# M310A.net
KiCad netlist of a schematic drawn in EAGLE
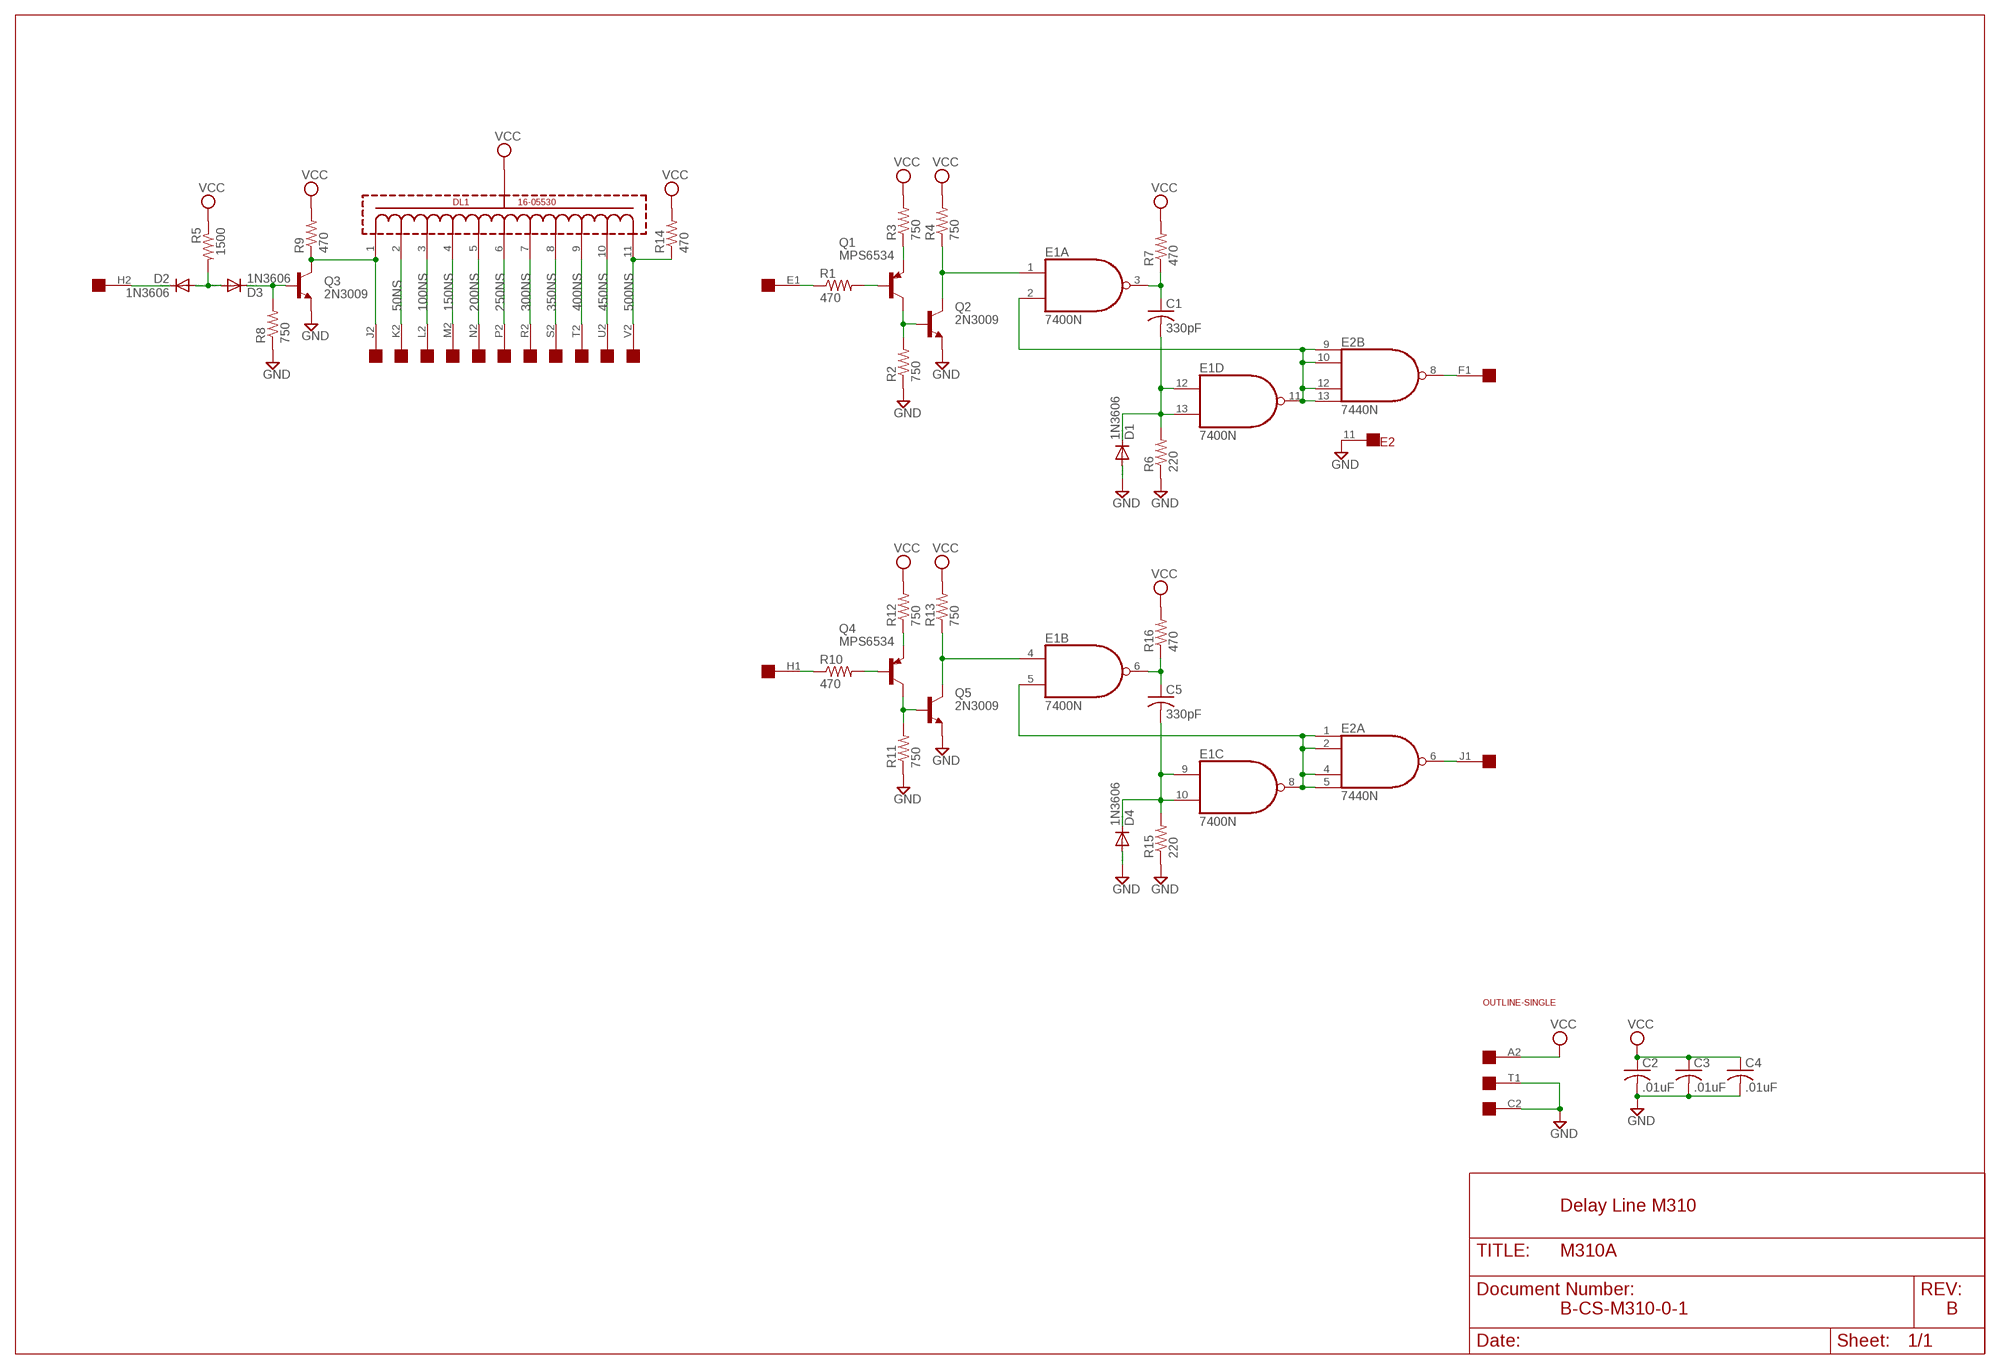
[diagram p0: schematic, sheet 1]

(export (version "E")
  (design (tool "Eeschema 10.0.6"))
  (components
    (comp (ref "C1")
      (value "330pF")
      (footprint "eagle-import:C050-025X075")
      (libsource (lib "eagle-import") (part "C-US050-025X075"))
    )
    (comp (ref "C2")
      (value ".01uF")
      (footprint "eagle-import:C050-025X075")
      (libsource (lib "eagle-import") (part "C-US050-025X075"))
    )
    (comp (ref "C3")
      (value ".01uF")
      (footprint "eagle-import:C050-025X075")
      (libsource (lib "eagle-import") (part "C-US050-025X075"))
    )
    (comp (ref "C4")
      (value ".01uF")
      (footprint "eagle-import:C050-025X075")
      (libsource (lib "eagle-import") (part "C-US050-025X075"))
    )
    (comp (ref "C5")
      (value "330pF")
      (footprint "eagle-import:C050-025X075")
      (libsource (lib "eagle-import") (part "C-US050-025X075"))
    )
    (comp (ref "D1")
      (value "1N3606")
      (footprint "eagle-import:DO35-10")
      (libsource (lib "eagle-import") (part "1N4148DO35-10"))
    )
    (comp (ref "D2")
      (value "1N3606")
      (footprint "eagle-import:DO35-10")
      (libsource (lib "eagle-import") (part "1N4148DO35-10"))
    )
    (comp (ref "D3")
      (value "1N3606")
      (footprint "eagle-import:DO35-10")
      (libsource (lib "eagle-import") (part "1N4148DO35-10"))
    )
    (comp (ref "D4")
      (value "1N3606")
      (footprint "eagle-import:DO35-10")
      (libsource (lib "eagle-import") (part "1N4148DO35-10"))
    )
    (comp (ref "DL1")
      (value "16-05530")
      (footprint "eagle-import:16-05530")
      (libsource (lib "eagle-import") (part "16-05530"))
    )
    (comp (ref "E1")
      (value "7400N")
      (footprint "eagle-import:DIL14")
      (libsource (lib "eagle-import") (part "7400N"))
    )
    (comp (ref "E2")
      (value "7440N")
      (footprint "eagle-import:DIL14")
      (libsource (lib "eagle-import") (part "7420NS"))
    )
    (comp (ref "Q1")
      (value "MPS6534")
      (footprint "eagle-import:TO39")
      (libsource (lib "eagle-import") (part "2N3637"))
    )
    (comp (ref "Q2")
      (value "2N3009")
      (footprint "eagle-import:TO39")
      (libsource (lib "eagle-import") (part "-NPN-TO39-EBC2N3019"))
    )
    (comp (ref "Q3")
      (value "2N3009")
      (footprint "eagle-import:TO39")
      (libsource (lib "eagle-import") (part "-NPN-TO39-EBC2N3019"))
    )
    (comp (ref "Q4")
      (value "MPS6534")
      (footprint "eagle-import:TO39")
      (libsource (lib "eagle-import") (part "2N3637"))
    )
    (comp (ref "Q5")
      (value "2N3009")
      (footprint "eagle-import:TO39")
      (libsource (lib "eagle-import") (part "-NPN-TO39-EBC2N3019"))
    )
    (comp (ref "R1")
      (value "470")
      (footprint "eagle-import:0207_10")
      (libsource (lib "eagle-import") (part "R-US_0207/10"))
    )
    (comp (ref "R2")
      (value "750")
      (footprint "eagle-import:0207_10")
      (libsource (lib "eagle-import") (part "R-US_0207/10"))
    )
    (comp (ref "R3")
      (value "750")
      (footprint "eagle-import:0207_10")
      (libsource (lib "eagle-import") (part "R-US_0207/10"))
    )
    (comp (ref "R4")
      (value "750")
      (footprint "eagle-import:0207_10")
      (libsource (lib "eagle-import") (part "R-US_0207/10"))
    )
    (comp (ref "R5")
      (value "1500")
      (footprint "eagle-import:0207_10")
      (libsource (lib "eagle-import") (part "R-US_0207/10"))
    )
    (comp (ref "R6")
      (value "220")
      (footprint "eagle-import:0207_10")
      (libsource (lib "eagle-import") (part "R-US_0207/10"))
    )
    (comp (ref "R7")
      (value "470")
      (footprint "eagle-import:0207_10")
      (libsource (lib "eagle-import") (part "R-US_0207/10"))
    )
    (comp (ref "R8")
      (value "750")
      (footprint "eagle-import:0207_10")
      (libsource (lib "eagle-import") (part "R-US_0207/10"))
    )
    (comp (ref "R9")
      (value "470")
      (footprint "eagle-import:0207_10")
      (libsource (lib "eagle-import") (part "R-US_0207/10"))
    )
    (comp (ref "R10")
      (value "470")
      (footprint "eagle-import:0207_10")
      (libsource (lib "eagle-import") (part "R-US_0207/10"))
    )
    (comp (ref "R11")
      (value "750")
      (footprint "eagle-import:0207_10")
      (libsource (lib "eagle-import") (part "R-US_0207/10"))
    )
    (comp (ref "R12")
      (value "750")
      (footprint "eagle-import:0207_10")
      (libsource (lib "eagle-import") (part "R-US_0207/10"))
    )
    (comp (ref "R13")
      (value "750")
      (footprint "eagle-import:0207_10")
      (libsource (lib "eagle-import") (part "R-US_0207/10"))
    )
    (comp (ref "R14")
      (value "470")
      (footprint "eagle-import:0207_10")
      (libsource (lib "eagle-import") (part "R-US_0207/10"))
    )
    (comp (ref "R15")
      (value "220")
      (footprint "eagle-import:0207_10")
      (libsource (lib "eagle-import") (part "R-US_0207/10"))
    )
    (comp (ref "R16")
      (value "470")
      (footprint "eagle-import:0207_10")
      (libsource (lib "eagle-import") (part "R-US_0207/10"))
    )
    (comp (ref "U$1")
      (value "OUTLINE-SINGLE")
      (footprint "eagle-import:SINGLE")
      (libsource (lib "eagle-import") (part "OUTLINE-SINGLE"))
    )
    (comp (ref "U$4")
      (value "SINGLE")
      (footprint "eagle-import:EDGE-CON2")
      (libsource (lib "eagle-import") (part "SINGLE"))
    )
  )
  (nets
    (net (code "1") (name "/50NS") (class "Default")
      (node (ref "DL1") (pin "2") (pinfunction "5_2") (pintype "passive"))
      (node (ref "U$4") (pin "K2") (pinfunction "1_K2") (pintype "bidirectional"))
    )
    (net (code "2") (name "/100NS") (class "Default")
      (node (ref "DL1") (pin "3") (pinfunction "10_3") (pintype "passive"))
      (node (ref "U$4") (pin "L2") (pinfunction "1_L2") (pintype "bidirectional"))
    )
    (net (code "3") (name "/150NS") (class "Default")
      (node (ref "DL1") (pin "4") (pinfunction "15_4") (pintype "passive"))
      (node (ref "U$4") (pin "M2") (pinfunction "1_M2") (pintype "bidirectional"))
    )
    (net (code "4") (name "/200NS") (class "Default")
      (node (ref "DL1") (pin "5") (pinfunction "20_5") (pintype "passive"))
      (node (ref "U$4") (pin "N2") (pinfunction "1_N2") (pintype "bidirectional"))
    )
    (net (code "5") (name "/250NS") (class "Default")
      (node (ref "DL1") (pin "6") (pinfunction "25_6") (pintype "passive"))
      (node (ref "U$4") (pin "P2") (pinfunction "1_P2") (pintype "bidirectional"))
    )
    (net (code "6") (name "/300NS") (class "Default")
      (node (ref "DL1") (pin "7") (pinfunction "30_7") (pintype "passive"))
      (node (ref "U$4") (pin "R2") (pinfunction "1_R2") (pintype "bidirectional"))
    )
    (net (code "7") (name "/350NS") (class "Default")
      (node (ref "DL1") (pin "8") (pinfunction "35_8") (pintype "passive"))
      (node (ref "U$4") (pin "S2") (pinfunction "1_S2") (pintype "bidirectional"))
    )
    (net (code "8") (name "/400NS") (class "Default")
      (node (ref "DL1") (pin "9") (pinfunction "40_9") (pintype "passive"))
      (node (ref "U$4") (pin "T2") (pinfunction "1_T2") (pintype "bidirectional"))
    )
    (net (code "9") (name "/450NS") (class "Default")
      (node (ref "DL1") (pin "10") (pinfunction "45_10") (pintype "passive"))
      (node (ref "U$4") (pin "U2") (pinfunction "1_U2") (pintype "bidirectional"))
    )
    (net (code "10") (name "/500NS") (class "Default")
      (node (ref "DL1") (pin "11") (pinfunction "50_11") (pintype "passive"))
      (node (ref "R14") (pin "1") (pinfunction "1_1") (pintype "passive"))
      (node (ref "U$4") (pin "V2") (pinfunction "1_V2") (pintype "bidirectional"))
    )
    (net (code "11") (name "GND") (class "Default")
      (node (ref "C2") (pin "2") (pinfunction "2_2") (pintype "passive"))
      (node (ref "C3") (pin "2") (pinfunction "2_2") (pintype "passive"))
      (node (ref "C4") (pin "2") (pinfunction "2_2") (pintype "passive"))
      (node (ref "D1") (pin "A") (pinfunction "A_A") (pintype "passive"))
      (node (ref "D4") (pin "A") (pinfunction "A_A") (pintype "passive"))
      (node (ref "E2") (pin "11") (pinfunction "NC_11") (pintype "passive"))
      (node (ref "Q2") (pin "1") (pinfunction "E_1") (pintype "passive"))
      (node (ref "Q3") (pin "1") (pinfunction "E_1") (pintype "passive"))
      (node (ref "Q5") (pin "1") (pinfunction "E_1") (pintype "passive"))
      (node (ref "R11") (pin "1") (pinfunction "1_1") (pintype "passive"))
      (node (ref "R15") (pin "1") (pinfunction "1_1") (pintype "passive"))
      (node (ref "R2") (pin "1") (pinfunction "1_1") (pintype "passive"))
      (node (ref "R6") (pin "1") (pinfunction "1_1") (pintype "passive"))
      (node (ref "R8") (pin "1") (pinfunction "1_1") (pintype "passive"))
      (node (ref "U$4") (pin "C2") (pinfunction "1_C2") (pintype "bidirectional"))
      (node (ref "U$4") (pin "T1") (pinfunction "1_T1") (pintype "bidirectional"))
    )
    (net (code "12") (name "Net-(D2-PadA)") (class "Default")
      (node (ref "D2") (pin "A") (pinfunction "A_A") (pintype "passive"))
      (node (ref "D3") (pin "A") (pinfunction "A_A") (pintype "passive"))
      (node (ref "R5") (pin "2") (pinfunction "2_2") (pintype "passive"))
    )
    (net (code "13") (name "Net-(DL1-0)") (class "Default")
      (node (ref "DL1") (pin "1") (pinfunction "0_1") (pintype "passive"))
      (node (ref "Q3") (pin "3") (pinfunction "C_3") (pintype "passive"))
      (node (ref "R9") (pin "1") (pinfunction "1_1") (pintype "passive"))
      (node (ref "U$4") (pin "J2") (pinfunction "1_J2") (pintype "bidirectional"))
    )
    (net (code "14") (name "Net-(E1A-I0)") (class "Default")
      (node (ref "E1") (pin "1") (pinfunction "I0_1") (pintype "input"))
      (node (ref "Q2") (pin "3") (pinfunction "C_3") (pintype "passive"))
      (node (ref "R4") (pin "1") (pinfunction "1_1") (pintype "passive"))
    )
    (net (code "15") (name "Net-(E1A-I1)") (class "Default")
      (node (ref "E1") (pin "11") (pinfunction "O_11") (pintype "output"))
      (node (ref "E1") (pin "2") (pinfunction "I1_2") (pintype "input"))
      (node (ref "E2") (pin "10") (pinfunction "I1_10") (pintype "input"))
      (node (ref "E2") (pin "12") (pinfunction "I2_12") (pintype "input"))
      (node (ref "E2") (pin "13") (pinfunction "I3_13") (pintype "input"))
      (node (ref "E2") (pin "9") (pinfunction "I0_9") (pintype "input"))
    )
    (net (code "16") (name "Net-(E1A-O)") (class "Default")
      (node (ref "C1") (pin "1") (pinfunction "1_1") (pintype "passive"))
      (node (ref "E1") (pin "3") (pinfunction "O_3") (pintype "output"))
      (node (ref "R7") (pin "1") (pinfunction "1_1") (pintype "passive"))
    )
    (net (code "17") (name "Net-(E1B-I0)") (class "Default")
      (node (ref "E1") (pin "4") (pinfunction "I0_4") (pintype "input"))
      (node (ref "Q5") (pin "3") (pinfunction "C_3") (pintype "passive"))
      (node (ref "R13") (pin "1") (pinfunction "1_1") (pintype "passive"))
    )
    (net (code "18") (name "Net-(E1B-I1)") (class "Default")
      (node (ref "E1") (pin "5") (pinfunction "I1_5") (pintype "input"))
      (node (ref "E1") (pin "8") (pinfunction "O_8") (pintype "output"))
      (node (ref "E2") (pin "1") (pinfunction "I0_1") (pintype "input"))
      (node (ref "E2") (pin "2") (pinfunction "I1_2") (pintype "input"))
      (node (ref "E2") (pin "4") (pinfunction "I2_4") (pintype "input"))
      (node (ref "E2") (pin "5") (pinfunction "I3_5") (pintype "input"))
    )
    (net (code "19") (name "Net-(E1B-O)") (class "Default")
      (node (ref "C5") (pin "1") (pinfunction "1_1") (pintype "passive"))
      (node (ref "E1") (pin "6") (pinfunction "O_6") (pintype "output"))
      (node (ref "R16") (pin "1") (pinfunction "1_1") (pintype "passive"))
    )
    (net (code "20") (name "Net-(E1C-I0)") (class "Default")
      (node (ref "C5") (pin "2") (pinfunction "2_2") (pintype "passive"))
      (node (ref "D4") (pin "C") (pinfunction "C_C") (pintype "passive"))
      (node (ref "E1") (pin "10") (pinfunction "I1_10") (pintype "input"))
      (node (ref "E1") (pin "9") (pinfunction "I0_9") (pintype "input"))
      (node (ref "R15") (pin "2") (pinfunction "2_2") (pintype "passive"))
    )
    (net (code "21") (name "Net-(E1D-I0)") (class "Default")
      (node (ref "C1") (pin "2") (pinfunction "2_2") (pintype "passive"))
      (node (ref "D1") (pin "C") (pinfunction "C_C") (pintype "passive"))
      (node (ref "E1") (pin "12") (pinfunction "I0_12") (pintype "input"))
      (node (ref "E1") (pin "13") (pinfunction "I1_13") (pintype "input"))
      (node (ref "R6") (pin "2") (pinfunction "2_2") (pintype "passive"))
    )
    (net (code "22") (name "Net-(E2C-O)") (class "Default")
      (node (ref "E2") (pin "6") (pinfunction "O_6") (pintype "output"))
      (node (ref "U$4") (pin "J1") (pinfunction "1_J1") (pintype "bidirectional"))
    )
    (net (code "23") (name "Net-(E2D-O)") (class "Default")
      (node (ref "E2") (pin "8") (pinfunction "O_8") (pintype "output"))
      (node (ref "U$4") (pin "F1") (pinfunction "1_F1") (pintype "bidirectional"))
    )
    (net (code "24") (name "Net-(Q1-B)") (class "Default")
      (node (ref "Q1") (pin "2") (pinfunction "B_2") (pintype "passive"))
      (node (ref "R1") (pin "2") (pinfunction "2_2") (pintype "passive"))
    )
    (net (code "25") (name "Net-(Q1-C)") (class "Default")
      (node (ref "Q1") (pin "3") (pinfunction "C_3") (pintype "passive"))
      (node (ref "Q2") (pin "2") (pinfunction "B_2") (pintype "passive"))
      (node (ref "R2") (pin "2") (pinfunction "2_2") (pintype "passive"))
    )
    (net (code "26") (name "Net-(Q1-E)") (class "Default")
      (node (ref "Q1") (pin "1") (pinfunction "E_1") (pintype "passive"))
      (node (ref "R3") (pin "1") (pinfunction "1_1") (pintype "passive"))
    )
    (net (code "27") (name "Net-(Q3-B)") (class "Default")
      (node (ref "D3") (pin "C") (pinfunction "C_C") (pintype "passive"))
      (node (ref "Q3") (pin "2") (pinfunction "B_2") (pintype "passive"))
      (node (ref "R8") (pin "2") (pinfunction "2_2") (pintype "passive"))
    )
    (net (code "28") (name "Net-(Q4-B)") (class "Default")
      (node (ref "Q4") (pin "2") (pinfunction "B_2") (pintype "passive"))
      (node (ref "R10") (pin "2") (pinfunction "2_2") (pintype "passive"))
    )
    (net (code "29") (name "Net-(Q4-C)") (class "Default")
      (node (ref "Q4") (pin "3") (pinfunction "C_3") (pintype "passive"))
      (node (ref "Q5") (pin "2") (pinfunction "B_2") (pintype "passive"))
      (node (ref "R11") (pin "2") (pinfunction "2_2") (pintype "passive"))
    )
    (net (code "30") (name "Net-(Q4-E)") (class "Default")
      (node (ref "Q4") (pin "1") (pinfunction "E_1") (pintype "passive"))
      (node (ref "R12") (pin "1") (pinfunction "1_1") (pintype "passive"))
    )
    (net (code "31") (name "Net-(U$4I-1)") (class "Default")
      (node (ref "R1") (pin "1") (pinfunction "1_1") (pintype "passive"))
      (node (ref "U$4") (pin "E1") (pinfunction "1_E1") (pintype "bidirectional"))
    )
    (net (code "32") (name "Net-(U$4M-1)") (class "Default")
      (node (ref "R10") (pin "1") (pinfunction "1_1") (pintype "passive"))
      (node (ref "U$4") (pin "H1") (pinfunction "1_H1") (pintype "bidirectional"))
    )
    (net (code "33") (name "Net-(U$4N-1)") (class "Default")
      (node (ref "D2") (pin "C") (pinfunction "C_C") (pintype "passive"))
      (node (ref "U$4") (pin "H2") (pinfunction "1_H2") (pintype "bidirectional"))
    )
    (net (code "34") (name "VCC") (class "Default")
      (node (ref "C2") (pin "1") (pinfunction "1_1") (pintype "passive"))
      (node (ref "C3") (pin "1") (pinfunction "1_1") (pintype "passive"))
      (node (ref "C4") (pin "1") (pinfunction "1_1") (pintype "passive"))
      (node (ref "DL1") (pin "12") (pinfunction "GND_12") (pintype "passive"))
      (node (ref "R12") (pin "2") (pinfunction "2_2") (pintype "passive"))
      (node (ref "R13") (pin "2") (pinfunction "2_2") (pintype "passive"))
      (node (ref "R14") (pin "2") (pinfunction "2_2") (pintype "passive"))
      (node (ref "R16") (pin "2") (pinfunction "2_2") (pintype "passive"))
      (node (ref "R3") (pin "2") (pinfunction "2_2") (pintype "passive"))
      (node (ref "R4") (pin "2") (pinfunction "2_2") (pintype "passive"))
      (node (ref "R5") (pin "1") (pinfunction "1_1") (pintype "passive"))
      (node (ref "R7") (pin "2") (pinfunction "2_2") (pintype "passive"))
      (node (ref "R9") (pin "2") (pinfunction "2_2") (pintype "passive"))
      (node (ref "U$4") (pin "A2") (pinfunction "1_A2") (pintype "bidirectional"))
    )
  )
)
